# Main.net
KiCad netlist of a schematic drawn in Altium Designer
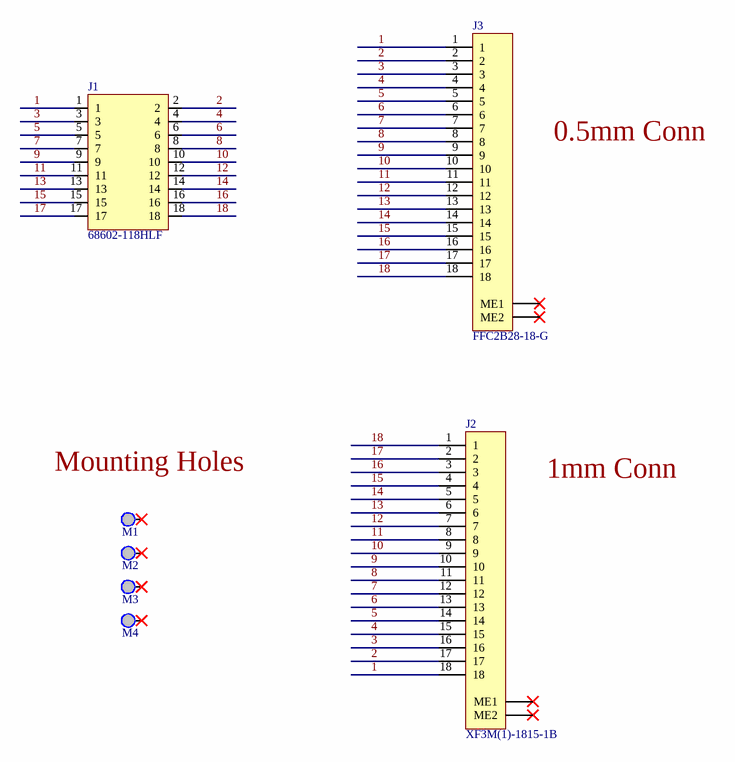
[diagram p0: Main.SchDoc]

(export (version "E")
  (design (tool "Eeschema 10.0.6"))
  (components
    (comp (ref "J1")
      (value "68602-118HLF")
      (footprint "HDR-V-2X9-2.54MM")
      (description "Conn Unshrouded Header HDR 18 POS 2.54mm Solder ST Top Entry Thru-Hole BergStik® Bulk")
      (libsource (lib "intercreate") (part "HDR-V-2X9-M-2.54MM"))
    )
    (comp (ref "J2")
      (value "XF3M(1)-1815-1B")
      (footprint "CONN-FFC-H-18P-1MM")
      (description "FFC & FPC Connectors RotaryBackLock 1.0mm Dual Contact 18pin")
      (libsource (lib "intercreate") (part "CONN-FFC-H-18P-1MM"))
    )
    (comp (ref "J3")
      (value "FFC2B28-18-G")
      (footprint "CONN-FFC-H-18P-0.5MM")
      (description "18W, 0.5MM Ffc Con, R/a, Dual Cont,")
      (libsource (lib "intercreate") (part "CONN-FFC-H-18P-0.5MM"))
    )
    (comp (ref "M1")
      (value "MTG_HOLE")
      (footprint "MH_P_2.5MM")
      (description "MTG HOLE PLATED VARIOUS SIZES")
      (libsource (lib "intercreate") (part "MTG_HOLE"))
    )
    (comp (ref "M2")
      (value "MTG_HOLE")
      (footprint "MH_P_2.5MM")
      (description "MTG HOLE PLATED VARIOUS SIZES")
      (libsource (lib "intercreate") (part "MTG_HOLE"))
    )
    (comp (ref "M3")
      (value "MTG_HOLE")
      (footprint "MH_P_2.5MM")
      (description "MTG HOLE PLATED VARIOUS SIZES")
      (libsource (lib "intercreate") (part "MTG_HOLE"))
    )
    (comp (ref "M4")
      (value "MTG_HOLE")
      (footprint "MH_P_2.5MM")
      (description "MTG HOLE PLATED VARIOUS SIZES")
      (libsource (lib "intercreate") (part "MTG_HOLE"))
    )
  )
  (nets
    (net (code "1") (name "/1") (class "Default")
      (node (ref "J1") (pin "1") (pinfunction "1_1") (pintype "passive"))
      (node (ref "J2") (pin "18") (pinfunction "18_18") (pintype "passive"))
      (node (ref "J3") (pin "1") (pinfunction "1_1") (pintype "passive"))
    )
    (net (code "2") (name "/2") (class "Default")
      (node (ref "J1") (pin "2") (pinfunction "2_2") (pintype "passive"))
      (node (ref "J2") (pin "17") (pinfunction "17_17") (pintype "passive"))
      (node (ref "J3") (pin "2") (pinfunction "2_2") (pintype "passive"))
    )
    (net (code "3") (name "/3") (class "Default")
      (node (ref "J1") (pin "3") (pinfunction "3_3") (pintype "passive"))
      (node (ref "J2") (pin "16") (pinfunction "16_16") (pintype "passive"))
      (node (ref "J3") (pin "3") (pinfunction "3_3") (pintype "passive"))
    )
    (net (code "4") (name "/4") (class "Default")
      (node (ref "J1") (pin "4") (pinfunction "4_4") (pintype "passive"))
      (node (ref "J2") (pin "15") (pinfunction "15_15") (pintype "passive"))
      (node (ref "J3") (pin "4") (pinfunction "4_4") (pintype "passive"))
    )
    (net (code "5") (name "/5") (class "Default")
      (node (ref "J1") (pin "5") (pinfunction "5_5") (pintype "passive"))
      (node (ref "J2") (pin "14") (pinfunction "14_14") (pintype "passive"))
      (node (ref "J3") (pin "5") (pinfunction "5_5") (pintype "passive"))
    )
    (net (code "6") (name "/6") (class "Default")
      (node (ref "J1") (pin "6") (pinfunction "6_6") (pintype "passive"))
      (node (ref "J2") (pin "13") (pinfunction "13_13") (pintype "passive"))
      (node (ref "J3") (pin "6") (pinfunction "6_6") (pintype "passive"))
    )
    (net (code "7") (name "/7") (class "Default")
      (node (ref "J1") (pin "7") (pinfunction "7_7") (pintype "passive"))
      (node (ref "J2") (pin "12") (pinfunction "12_12") (pintype "passive"))
      (node (ref "J3") (pin "7") (pinfunction "7_7") (pintype "passive"))
    )
    (net (code "8") (name "/8") (class "Default")
      (node (ref "J1") (pin "8") (pinfunction "8_8") (pintype "passive"))
      (node (ref "J2") (pin "11") (pinfunction "11_11") (pintype "passive"))
      (node (ref "J3") (pin "8") (pinfunction "8_8") (pintype "passive"))
    )
    (net (code "9") (name "/9") (class "Default")
      (node (ref "J1") (pin "9") (pinfunction "9_9") (pintype "passive"))
      (node (ref "J2") (pin "10") (pinfunction "10_10") (pintype "passive"))
      (node (ref "J3") (pin "9") (pinfunction "9_9") (pintype "passive"))
    )
    (net (code "10") (name "/10") (class "Default")
      (node (ref "J1") (pin "10") (pinfunction "10_10") (pintype "passive"))
      (node (ref "J2") (pin "9") (pinfunction "9_9") (pintype "passive"))
      (node (ref "J3") (pin "10") (pinfunction "10_10") (pintype "passive"))
    )
    (net (code "11") (name "/11") (class "Default")
      (node (ref "J1") (pin "11") (pinfunction "11_11") (pintype "passive"))
      (node (ref "J2") (pin "8") (pinfunction "8_8") (pintype "passive"))
      (node (ref "J3") (pin "11") (pinfunction "11_11") (pintype "passive"))
    )
    (net (code "12") (name "/12") (class "Default")
      (node (ref "J1") (pin "12") (pinfunction "12_12") (pintype "passive"))
      (node (ref "J2") (pin "7") (pinfunction "7_7") (pintype "passive"))
      (node (ref "J3") (pin "12") (pinfunction "12_12") (pintype "passive"))
    )
    (net (code "13") (name "/13") (class "Default")
      (node (ref "J1") (pin "13") (pinfunction "13_13") (pintype "passive"))
      (node (ref "J2") (pin "6") (pinfunction "6_6") (pintype "passive"))
      (node (ref "J3") (pin "13") (pinfunction "13_13") (pintype "passive"))
    )
    (net (code "14") (name "/14") (class "Default")
      (node (ref "J1") (pin "14") (pinfunction "14_14") (pintype "passive"))
      (node (ref "J2") (pin "5") (pinfunction "5_5") (pintype "passive"))
      (node (ref "J3") (pin "14") (pinfunction "14_14") (pintype "passive"))
    )
    (net (code "15") (name "/15") (class "Default")
      (node (ref "J1") (pin "15") (pinfunction "15_15") (pintype "passive"))
      (node (ref "J2") (pin "4") (pinfunction "4_4") (pintype "passive"))
      (node (ref "J3") (pin "15") (pinfunction "15_15") (pintype "passive"))
    )
    (net (code "16") (name "/16") (class "Default")
      (node (ref "J1") (pin "16") (pinfunction "16_16") (pintype "passive"))
      (node (ref "J2") (pin "3") (pinfunction "3_3") (pintype "passive"))
      (node (ref "J3") (pin "16") (pinfunction "16_16") (pintype "passive"))
    )
    (net (code "17") (name "/17") (class "Default")
      (node (ref "J1") (pin "17") (pinfunction "17_17") (pintype "passive"))
      (node (ref "J2") (pin "2") (pinfunction "2_2") (pintype "passive"))
      (node (ref "J3") (pin "17") (pinfunction "17_17") (pintype "passive"))
    )
    (net (code "18") (name "/18") (class "Default")
      (node (ref "J1") (pin "18") (pinfunction "18_18") (pintype "passive"))
      (node (ref "J2") (pin "1") (pinfunction "1_1") (pintype "passive"))
      (node (ref "J3") (pin "18") (pinfunction "18_18") (pintype "passive"))
    )
    (net (code "19") (name "unconnected-(J2-PadME1)") (class "Default")
      (node (ref "J2") (pin "ME1") (pinfunction "ME1_ME1") (pintype "passive+no_connect"))
    )
    (net (code "20") (name "unconnected-(J2-PadME2)") (class "Default")
      (node (ref "J2") (pin "ME2") (pinfunction "ME2_ME2") (pintype "passive+no_connect"))
    )
    (net (code "21") (name "unconnected-(J3-PadME1)") (class "Default")
      (node (ref "J3") (pin "ME1") (pinfunction "ME1_ME1") (pintype "passive+no_connect"))
    )
    (net (code "22") (name "unconnected-(J3-PadME2)") (class "Default")
      (node (ref "J3") (pin "ME2") (pinfunction "ME2_ME2") (pintype "passive+no_connect"))
    )
    (net (code "23") (name "unconnected-(M1-Pad1)") (class "Default")
      (node (ref "M1") (pin "1") (pinfunction "1_1") (pintype "passive+no_connect"))
    )
    (net (code "24") (name "unconnected-(M2-Pad1)") (class "Default")
      (node (ref "M2") (pin "1") (pinfunction "1_1") (pintype "passive+no_connect"))
    )
    (net (code "25") (name "unconnected-(M3-Pad1)") (class "Default")
      (node (ref "M3") (pin "1") (pinfunction "1_1") (pintype "passive+no_connect"))
    )
    (net (code "26") (name "unconnected-(M4-Pad1)") (class "Default")
      (node (ref "M4") (pin "1") (pinfunction "1_1") (pintype "passive+no_connect"))
    )
  )
)
